# Pcb8led.net
KiCad netlist of a schematic drawn in Altium Designer
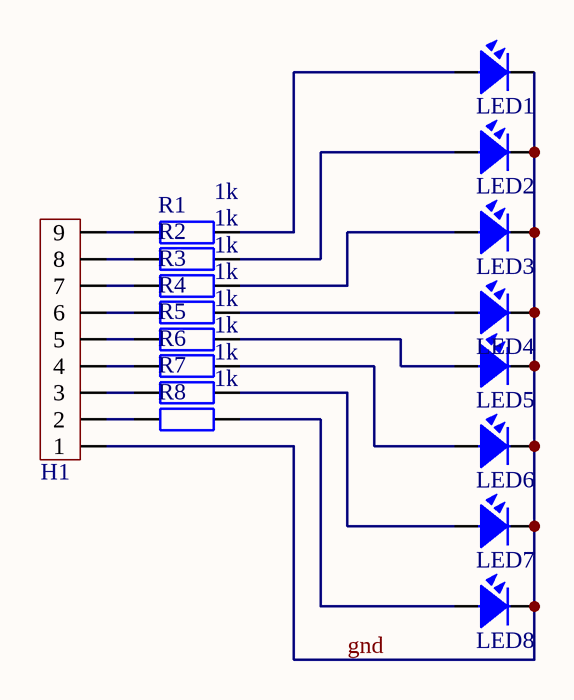
[diagram p0: Pcb8led.SchDoc]

(export (version "E")
  (design (tool "Eeschema 10.0.6"))
  (components
    (comp (ref "H1")
      (value "Header9")
      (footprint "Header9")
      (description "Header IDC, 9 x 1 Pin Vertical 2.54mm Pitch (Non-Boxed, Male)")
      (libsource (lib "LIBRARY") (part "Header9"))
    )
    (comp (ref "LED1")
      (value "LED")
      (footprint "LED-3")
      (description "LED Single colour Green and Red")
      (libsource (lib "syhaunguyen") (part "LED"))
    )
    (comp (ref "LED2")
      (value "LED")
      (footprint "LED-3")
      (description "LED Single colour Green and Red")
      (libsource (lib "syhaunguyen") (part "LED"))
    )
    (comp (ref "LED3")
      (value "LED")
      (footprint "LED-3")
      (description "LED Single colour Green and Red")
      (libsource (lib "syhaunguyen") (part "LED"))
    )
    (comp (ref "LED4")
      (value "LED")
      (footprint "LED-3")
      (description "LED Single colour Green and Red")
      (libsource (lib "syhaunguyen") (part "LED"))
    )
    (comp (ref "LED5")
      (value "LED")
      (footprint "LED-3")
      (description "LED Single colour Green and Red")
      (libsource (lib "syhaunguyen") (part "LED"))
    )
    (comp (ref "LED6")
      (value "LED")
      (footprint "LED-3")
      (description "LED Single colour Green and Red")
      (libsource (lib "syhaunguyen") (part "LED"))
    )
    (comp (ref "LED7")
      (value "LED")
      (footprint "LED-3")
      (description "LED Single colour Green and Red")
      (libsource (lib "syhaunguyen") (part "LED"))
    )
    (comp (ref "LED8")
      (value "LED")
      (footprint "LED-3")
      (description "LED Single colour Green and Red")
      (libsource (lib "syhaunguyen") (part "LED"))
    )
    (comp (ref "R1")
      (value "1k")
      (footprint "R1/4W")
      (description "Resistor 1/4W")
      (libsource (lib "syhaunguyen") (part "R1/4W"))
    )
    (comp (ref "R2")
      (value "1k")
      (footprint "R1/4W")
      (description "Resistor 1/4W")
      (libsource (lib "syhaunguyen") (part "R1/4W"))
    )
    (comp (ref "R3")
      (value "1k")
      (footprint "R1/4W")
      (description "Resistor 1/4W")
      (libsource (lib "syhaunguyen") (part "R1/4W"))
    )
    (comp (ref "R4")
      (value "1k")
      (footprint "R1/4W")
      (description "Resistor 1/4W")
      (libsource (lib "syhaunguyen") (part "R1/4W"))
    )
    (comp (ref "R5")
      (value "1k")
      (footprint "R1/4W")
      (description "Resistor 1/4W")
      (libsource (lib "syhaunguyen") (part "R1/4W"))
    )
    (comp (ref "R6")
      (value "1k")
      (footprint "R1/4W")
      (description "Resistor 1/4W")
      (libsource (lib "syhaunguyen") (part "R1/4W"))
    )
    (comp (ref "R7")
      (value "1k")
      (footprint "R1/4W")
      (description "Resistor 1/4W")
      (libsource (lib "syhaunguyen") (part "R1/4W"))
    )
    (comp (ref "R8")
      (value "1k")
      (footprint "R1/4W")
      (description "Resistor 1/4W")
      (libsource (lib "syhaunguyen") (part "R1/4W"))
    )
  )
  (nets
    (net (code "1") (name "/gnd") (class "Default")
      (node (ref "H1") (pin "1") (pinfunction "1_1") (pintype "passive"))
      (node (ref "LED1") (pin "2") (pinfunction "2_2") (pintype "passive"))
      (node (ref "LED2") (pin "2") (pinfunction "2_2") (pintype "passive"))
      (node (ref "LED3") (pin "2") (pinfunction "2_2") (pintype "passive"))
      (node (ref "LED4") (pin "2") (pinfunction "2_2") (pintype "passive"))
      (node (ref "LED5") (pin "2") (pinfunction "2_2") (pintype "passive"))
      (node (ref "LED6") (pin "2") (pinfunction "2_2") (pintype "passive"))
      (node (ref "LED7") (pin "2") (pinfunction "2_2") (pintype "passive"))
      (node (ref "LED8") (pin "2") (pinfunction "2_2") (pintype "passive"))
    )
    (net (code "2") (name "Net-(H1-Pad2)") (class "Default")
      (node (ref "H1") (pin "2") (pinfunction "2_2") (pintype "passive"))
      (node (ref "R8") (pin "1") (pinfunction "1_1") (pintype "passive"))
    )
    (net (code "3") (name "Net-(H1-Pad3)") (class "Default")
      (node (ref "H1") (pin "3") (pinfunction "3_3") (pintype "passive"))
      (node (ref "R7") (pin "1") (pinfunction "1_1") (pintype "passive"))
    )
    (net (code "4") (name "Net-(H1-Pad4)") (class "Default")
      (node (ref "H1") (pin "4") (pinfunction "4_4") (pintype "passive"))
      (node (ref "R6") (pin "1") (pinfunction "1_1") (pintype "passive"))
    )
    (net (code "5") (name "Net-(H1-Pad5)") (class "Default")
      (node (ref "H1") (pin "5") (pinfunction "5_5") (pintype "passive"))
      (node (ref "R5") (pin "1") (pinfunction "1_1") (pintype "passive"))
    )
    (net (code "6") (name "Net-(H1-Pad6)") (class "Default")
      (node (ref "H1") (pin "6") (pinfunction "6_6") (pintype "passive"))
      (node (ref "R4") (pin "1") (pinfunction "1_1") (pintype "passive"))
    )
    (net (code "7") (name "Net-(H1-Pad7)") (class "Default")
      (node (ref "H1") (pin "7") (pinfunction "7_7") (pintype "passive"))
      (node (ref "R3") (pin "1") (pinfunction "1_1") (pintype "passive"))
    )
    (net (code "8") (name "Net-(H1-Pad8)") (class "Default")
      (node (ref "H1") (pin "8") (pinfunction "8_8") (pintype "passive"))
      (node (ref "R2") (pin "1") (pinfunction "1_1") (pintype "passive"))
    )
    (net (code "9") (name "Net-(H1-Pad9)") (class "Default")
      (node (ref "H1") (pin "9") (pinfunction "9_9") (pintype "passive"))
      (node (ref "R1") (pin "1") (pinfunction "1_1") (pintype "passive"))
    )
    (net (code "10") (name "Net-(LED1-Pad1)") (class "Default")
      (node (ref "LED1") (pin "1") (pinfunction "1_1") (pintype "passive"))
      (node (ref "R1") (pin "2") (pinfunction "2_2") (pintype "passive"))
    )
    (net (code "11") (name "Net-(LED2-Pad1)") (class "Default")
      (node (ref "LED2") (pin "1") (pinfunction "1_1") (pintype "passive"))
      (node (ref "R2") (pin "2") (pinfunction "2_2") (pintype "passive"))
    )
    (net (code "12") (name "Net-(LED3-Pad1)") (class "Default")
      (node (ref "LED3") (pin "1") (pinfunction "1_1") (pintype "passive"))
      (node (ref "R3") (pin "2") (pinfunction "2_2") (pintype "passive"))
    )
    (net (code "13") (name "Net-(LED4-Pad1)") (class "Default")
      (node (ref "LED4") (pin "1") (pinfunction "1_1") (pintype "passive"))
      (node (ref "R4") (pin "2") (pinfunction "2_2") (pintype "passive"))
    )
    (net (code "14") (name "Net-(LED5-Pad1)") (class "Default")
      (node (ref "LED5") (pin "1") (pinfunction "1_1") (pintype "passive"))
      (node (ref "R5") (pin "2") (pinfunction "2_2") (pintype "passive"))
    )
    (net (code "15") (name "Net-(LED6-Pad1)") (class "Default")
      (node (ref "LED6") (pin "1") (pinfunction "1_1") (pintype "passive"))
      (node (ref "R6") (pin "2") (pinfunction "2_2") (pintype "passive"))
    )
    (net (code "16") (name "Net-(LED7-Pad1)") (class "Default")
      (node (ref "LED7") (pin "1") (pinfunction "1_1") (pintype "passive"))
      (node (ref "R7") (pin "2") (pinfunction "2_2") (pintype "passive"))
    )
    (net (code "17") (name "Net-(LED8-Pad1)") (class "Default")
      (node (ref "LED8") (pin "1") (pinfunction "1_1") (pintype "passive"))
      (node (ref "R8") (pin "2") (pinfunction "2_2") (pintype "passive"))
    )
  )
)
